# STM32F050F_Base.net
KiCad netlist of a schematic drawn in EAGLE
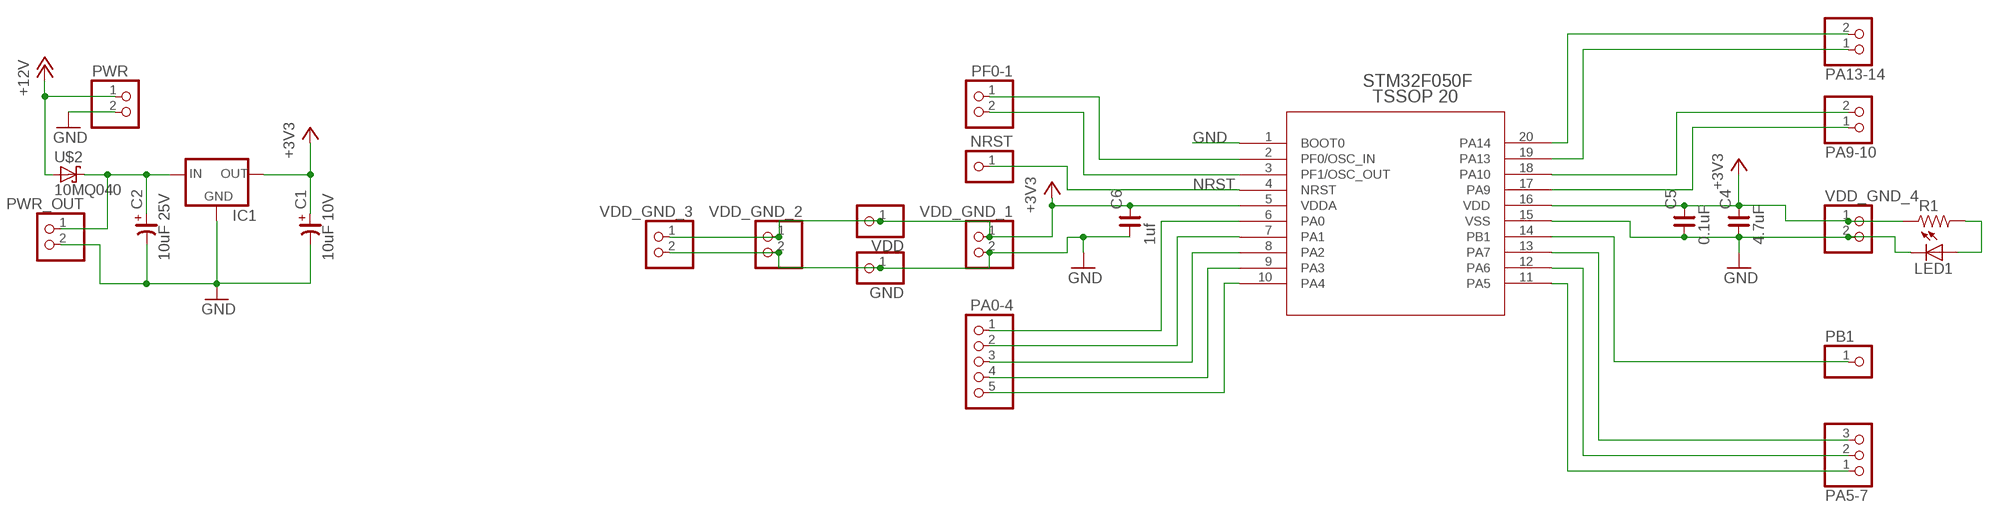
[diagram p0: schematic, sheet 1]

(export (version "E")
  (design (tool "Eeschema 10.0.6"))
  (components
    (comp (ref "C1")
      (value "10uF 10V")
      (footprint "eagle-import:C3216-18_T")
      (libsource (lib "eagle-import") (part "CP_3216-18"))
    )
    (comp (ref "C2")
      (value "10uF 25V")
      (footprint "eagle-import:C3528-21_T")
      (libsource (lib "eagle-import") (part "CP_3528-21"))
    )
    (comp (ref "C4")
      (value "4.7uF")
      (footprint "eagle-import:C1206")
      (libsource (lib "eagle-import") (part "C_1206"))
    )
    (comp (ref "C5")
      (value "0.1uF")
      (footprint "eagle-import:C0805")
      (libsource (lib "eagle-import") (part "C_0805"))
    )
    (comp (ref "C6")
      (value "1uf")
      (footprint "eagle-import:C0805")
      (libsource (lib "eagle-import") (part "C_0805"))
    )
    (comp (ref "GND")
      (value "PINHD-1X01_2.54-S")
      (footprint "eagle-import:1X01-S")
      (libsource (lib "eagle-import") (part "PINHD-1X01_2.54-S"))
    )
    (comp (ref "IC1")
      (value "LM1117")
      (footprint "eagle-import:SOT223")
      (libsource (lib "eagle-import") (part "LM1117"))
    )
    (comp (ref "LED1")
      (value "LEDCHIP-LED0805")
      (footprint "eagle-import:CHIP-LED0805")
      (libsource (lib "eagle-import") (part "LEDCHIP-LED0805"))
    )
    (comp (ref "NRST")
      (value "PINHD-1X01_2.54-S")
      (footprint "eagle-import:1X01-S")
      (libsource (lib "eagle-import") (part "PINHD-1X01_2.54-S"))
    )
    (comp (ref "PA0-4")
      (value "PINHD-1X05_2.54-S")
      (footprint "eagle-import:1X05-S")
      (libsource (lib "eagle-import") (part "PINHD-1X05_2.54-S"))
    )
    (comp (ref "PA5-7")
      (value "PINHD-1X03_2.54-S")
      (footprint "eagle-import:1X03-S")
      (libsource (lib "eagle-import") (part "PINHD-1X03_2.54-S"))
    )
    (comp (ref "PA9-10")
      (value "PINHD-1X02_2.54-S")
      (footprint "eagle-import:1X02-S")
      (libsource (lib "eagle-import") (part "PINHD-1X02_2.54-S"))
    )
    (comp (ref "PA13-14")
      (value "PINHD-1X02_2.54-S")
      (footprint "eagle-import:1X02-S")
      (libsource (lib "eagle-import") (part "PINHD-1X02_2.54-S"))
    )
    (comp (ref "PB1")
      (value "PINHD-1X01_2.54-S")
      (footprint "eagle-import:1X01-S")
      (libsource (lib "eagle-import") (part "PINHD-1X01_2.54-S"))
    )
    (comp (ref "PF0-1")
      (value "PINHD-1X02_2.54-S")
      (footprint "eagle-import:1X02-S")
      (libsource (lib "eagle-import") (part "PINHD-1X02_2.54-S"))
    )
    (comp (ref "PWR")
      (value "PINHD-1X02_2.54-90°-S")
      (footprint "eagle-import:1X02_90-S")
      (libsource (lib "eagle-import") (part "PINHD-1X02_2.54-90°-S"))
    )
    (comp (ref "PWR_OUT")
      (value "PINHD-1X02_2.54-S")
      (footprint "eagle-import:1X02-S")
      (libsource (lib "eagle-import") (part "PINHD-1X02_2.54-S"))
    )
    (comp (ref "R1")
      (value "R_0805")
      (footprint "eagle-import:R0805")
      (libsource (lib "eagle-import") (part "R_0805"))
    )
    (comp (ref "U$1")
      (value "STM32F050F4P6")
      (footprint "eagle-import:TSSOP20")
      (libsource (lib "eagle-import") (part "STM32F050F4P6"))
    )
    (comp (ref "U$2")
      (value "10MQ040")
      (footprint "eagle-import:SMA")
      (libsource (lib "eagle-import") (part "10MQ040"))
    )
    (comp (ref "VDD")
      (value "PINHD-1X01_2.54-S")
      (footprint "eagle-import:1X01-S")
      (libsource (lib "eagle-import") (part "PINHD-1X01_2.54-S"))
    )
    (comp (ref "VDD_GND_1")
      (value "PINHD-1X02_2.54-S")
      (footprint "eagle-import:1X02-S")
      (libsource (lib "eagle-import") (part "PINHD-1X02_2.54-S"))
    )
    (comp (ref "VDD_GND_2")
      (value "PINHD-1X02_2.54-S")
      (footprint "eagle-import:1X02-S")
      (libsource (lib "eagle-import") (part "PINHD-1X02_2.54-S"))
    )
    (comp (ref "VDD_GND_3")
      (value "PINHD-1X02_2.54-S")
      (footprint "eagle-import:1X02-S")
      (libsource (lib "eagle-import") (part "PINHD-1X02_2.54-S"))
    )
    (comp (ref "VDD_GND_4")
      (value "PINHD-1X02_2.54-S")
      (footprint "eagle-import:1X02-S")
      (libsource (lib "eagle-import") (part "PINHD-1X02_2.54-S"))
    )
  )
  (nets
    (net (code "1") (name "+3V3") (class "Default")
      (node (ref "C1") (pin "+") (pinfunction "+_+") (pintype "passive"))
      (node (ref "C4") (pin "2") (pinfunction "2_2") (pintype "passive"))
      (node (ref "C5") (pin "2") (pinfunction "2_2") (pintype "passive"))
      (node (ref "C6") (pin "2") (pinfunction "2_2") (pintype "passive"))
      (node (ref "IC1") (pin "2") (pinfunction "OUT_2") (pintype "passive"))
      (node (ref "R1") (pin "1") (pinfunction "1_1") (pintype "passive"))
      (node (ref "U$1") (pin "16") (pinfunction "VDD_16") (pintype "passive"))
      (node (ref "U$1") (pin "5") (pinfunction "VDDA_5") (pintype "passive"))
      (node (ref "VDD") (pin "1") (pinfunction "1_1") (pintype "passive"))
      (node (ref "VDD_GND_1") (pin "1") (pinfunction "1_1") (pintype "passive"))
      (node (ref "VDD_GND_2") (pin "1") (pinfunction "1_1") (pintype "passive"))
      (node (ref "VDD_GND_3") (pin "1") (pinfunction "1_1") (pintype "passive"))
      (node (ref "VDD_GND_4") (pin "1") (pinfunction "1_1") (pintype "passive"))
    )
    (net (code "2") (name "+12V") (class "Default")
      (node (ref "PWR") (pin "1") (pinfunction "1_1") (pintype "passive"))
      (node (ref "U$2") (pin "A") (pinfunction "A_A") (pintype "passive"))
    )
    (net (code "3") (name "/NRST") (class "Default")
      (node (ref "NRST") (pin "1") (pinfunction "1_1") (pintype "passive"))
      (node (ref "U$1") (pin "4") (pinfunction "NRST_4") (pintype "passive"))
    )
    (net (code "4") (name "GND") (class "Default")
      (node (ref "C1") (pin "-") (pinfunction "-_-") (pintype "passive"))
      (node (ref "C2") (pin "-") (pinfunction "-_-") (pintype "passive"))
      (node (ref "C4") (pin "1") (pinfunction "1_1") (pintype "passive"))
      (node (ref "C5") (pin "1") (pinfunction "1_1") (pintype "passive"))
      (node (ref "C6") (pin "1") (pinfunction "1_1") (pintype "passive"))
      (node (ref "GND") (pin "1") (pinfunction "1_1") (pintype "passive"))
      (node (ref "IC1") (pin "1") (pinfunction "GND_1") (pintype "input"))
      (node (ref "LED1") (pin "C") (pinfunction "C_C") (pintype "passive"))
      (node (ref "PWR") (pin "2") (pinfunction "2_2") (pintype "passive"))
      (node (ref "PWR_OUT") (pin "2") (pinfunction "2_2") (pintype "passive"))
      (node (ref "U$1") (pin "1") (pinfunction "BOOT0_1") (pintype "passive"))
      (node (ref "U$1") (pin "15") (pinfunction "VSS_15") (pintype "passive"))
      (node (ref "VDD_GND_1") (pin "2") (pinfunction "2_2") (pintype "passive"))
      (node (ref "VDD_GND_2") (pin "2") (pinfunction "2_2") (pintype "passive"))
      (node (ref "VDD_GND_3") (pin "2") (pinfunction "2_2") (pintype "passive"))
      (node (ref "VDD_GND_4") (pin "2") (pinfunction "2_2") (pintype "passive"))
    )
    (net (code "5") (name "Net-(IC1-IN)") (class "Default")
      (node (ref "C2") (pin "+") (pinfunction "+_+") (pintype "passive"))
      (node (ref "IC1") (pin "3") (pinfunction "IN_3") (pintype "input"))
      (node (ref "PWR_OUT") (pin "1") (pinfunction "1_1") (pintype "passive"))
      (node (ref "U$2") (pin "C") (pinfunction "C_C") (pintype "passive"))
    )
    (net (code "6") (name "Net-(LED1-PadA)") (class "Default")
      (node (ref "LED1") (pin "A") (pinfunction "A_A") (pintype "passive"))
      (node (ref "R1") (pin "2") (pinfunction "2_2") (pintype "passive"))
    )
    (net (code "7") (name "Net-(U$1-PA0)") (class "Default")
      (node (ref "PA0-4") (pin "1") (pinfunction "1_1") (pintype "passive"))
      (node (ref "U$1") (pin "6") (pinfunction "PA0_6") (pintype "passive"))
    )
    (net (code "8") (name "Net-(U$1-PA1)") (class "Default")
      (node (ref "PA0-4") (pin "2") (pinfunction "2_2") (pintype "passive"))
      (node (ref "U$1") (pin "7") (pinfunction "PA1_7") (pintype "passive"))
    )
    (net (code "9") (name "Net-(U$1-PA2)") (class "Default")
      (node (ref "PA0-4") (pin "3") (pinfunction "3_3") (pintype "passive"))
      (node (ref "U$1") (pin "8") (pinfunction "PA2_8") (pintype "passive"))
    )
    (net (code "10") (name "Net-(U$1-PA3)") (class "Default")
      (node (ref "PA0-4") (pin "4") (pinfunction "4_4") (pintype "passive"))
      (node (ref "U$1") (pin "9") (pinfunction "PA3_9") (pintype "passive"))
    )
    (net (code "11") (name "Net-(U$1-PA4)") (class "Default")
      (node (ref "PA0-4") (pin "5") (pinfunction "5_5") (pintype "passive"))
      (node (ref "U$1") (pin "10") (pinfunction "PA4_10") (pintype "passive"))
    )
    (net (code "12") (name "Net-(U$1-PA5)") (class "Default")
      (node (ref "PA5-7") (pin "1") (pinfunction "1_1") (pintype "passive"))
      (node (ref "U$1") (pin "11") (pinfunction "PA5_11") (pintype "passive"))
    )
    (net (code "13") (name "Net-(U$1-PA6)") (class "Default")
      (node (ref "PA5-7") (pin "2") (pinfunction "2_2") (pintype "passive"))
      (node (ref "U$1") (pin "12") (pinfunction "PA6_12") (pintype "passive"))
    )
    (net (code "14") (name "Net-(U$1-PA7)") (class "Default")
      (node (ref "PA5-7") (pin "3") (pinfunction "3_3") (pintype "passive"))
      (node (ref "U$1") (pin "13") (pinfunction "PA7_13") (pintype "passive"))
    )
    (net (code "15") (name "Net-(U$1-PA9)") (class "Default")
      (node (ref "PA9-10") (pin "1") (pinfunction "1_1") (pintype "passive"))
      (node (ref "U$1") (pin "17") (pinfunction "PA9_17") (pintype "passive"))
    )
    (net (code "16") (name "Net-(U$1-PA10)") (class "Default")
      (node (ref "PA9-10") (pin "2") (pinfunction "2_2") (pintype "passive"))
      (node (ref "U$1") (pin "18") (pinfunction "PA10_18") (pintype "passive"))
    )
    (net (code "17") (name "Net-(U$1-PA13)") (class "Default")
      (node (ref "PA13-14") (pin "1") (pinfunction "1_1") (pintype "passive"))
      (node (ref "U$1") (pin "19") (pinfunction "PA13_19") (pintype "passive"))
    )
    (net (code "18") (name "Net-(U$1-PA14)") (class "Default")
      (node (ref "PA13-14") (pin "2") (pinfunction "2_2") (pintype "passive"))
      (node (ref "U$1") (pin "20") (pinfunction "PA14_20") (pintype "passive"))
    )
    (net (code "19") (name "Net-(U$1-PB1)") (class "Default")
      (node (ref "PB1") (pin "1") (pinfunction "1_1") (pintype "passive"))
      (node (ref "U$1") (pin "14") (pinfunction "PB1_14") (pintype "passive"))
    )
    (net (code "20") (name "Net-(U$1-PF0{slash}OSC_IN)") (class "Default")
      (node (ref "PF0-1") (pin "1") (pinfunction "1_1") (pintype "passive"))
      (node (ref "U$1") (pin "2") (pinfunction "PF0/OSC_IN_2") (pintype "passive"))
    )
    (net (code "21") (name "Net-(U$1-PF1{slash}OSC_OUT)") (class "Default")
      (node (ref "PF0-1") (pin "2") (pinfunction "2_2") (pintype "passive"))
      (node (ref "U$1") (pin "3") (pinfunction "PF1/OSC_OUT_3") (pintype "passive"))
    )
  )
)
